# Sensor.net
KiCad netlist of a schematic drawn in Altium Designer
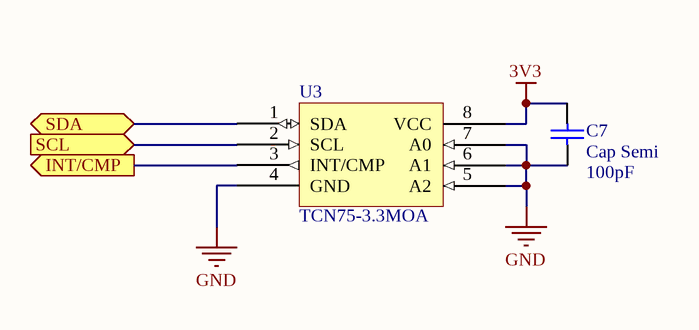
[diagram p0: Sensor.SchDoc]

(export (version "E")
  (design (tool "Eeschema 10.0.6"))
  (components
    (comp (ref "C7")
      (value "Cap Semi")
      (footprint "0603_C")
      (description "Capacitor (Semiconductor SIM Model)")
      (fields (field (name "ALTIUM_VALUE") "100pF") (field (name "PUBLISHER") "Altium Limited"))
      (libsource (lib "Miscellaneous Devices") (part "Cap Semi"))
    )
    (comp (ref "U3")
      (value "TCN75-3.3MOA")
      (footprint "SOIC-8_150mil")
      (description "TCN75数字温度传感器将-40°C到+125°C范围内的温度转换为数字")
      (libsource (lib "ad_test2_IntLib") (part "TCN75"))
    )
  )
  (nets
    (net (code "1") (name "/INT{slash}CMP") (class "Default")
      (node (ref "U3") (pin "3") (pinfunction "INT/CMP_3") (pintype "output"))
    )
    (net (code "2") (name "/SCL") (class "Default")
      (node (ref "U3") (pin "2") (pinfunction "SCL_2") (pintype "input"))
    )
    (net (code "3") (name "/SDA") (class "Default")
      (node (ref "U3") (pin "1") (pinfunction "SDA_1") (pintype "bidirectional"))
    )
    (net (code "4") (name "3V3") (class "Default")
      (node (ref "C7") (pin "2") (pinfunction "2_2") (pintype "passive"))
      (node (ref "U3") (pin "8") (pinfunction "VCC_8") (pintype "power_in"))
    )
    (net (code "5") (name "GND") (class "Default")
      (node (ref "C7") (pin "1") (pinfunction "1_1") (pintype "passive"))
      (node (ref "U3") (pin "4") (pinfunction "GND_4") (pintype "power_in"))
      (node (ref "U3") (pin "5") (pinfunction "A2_5") (pintype "input"))
      (node (ref "U3") (pin "6") (pinfunction "A1_6") (pintype "input"))
      (node (ref "U3") (pin "7") (pinfunction "A0_7") (pintype "input"))
    )
  )
)
